# UBC-Thunderbots_PCB_Power__power-v3_1_pc.net
KiCad netlist of a schematic drawn in Altium Designer
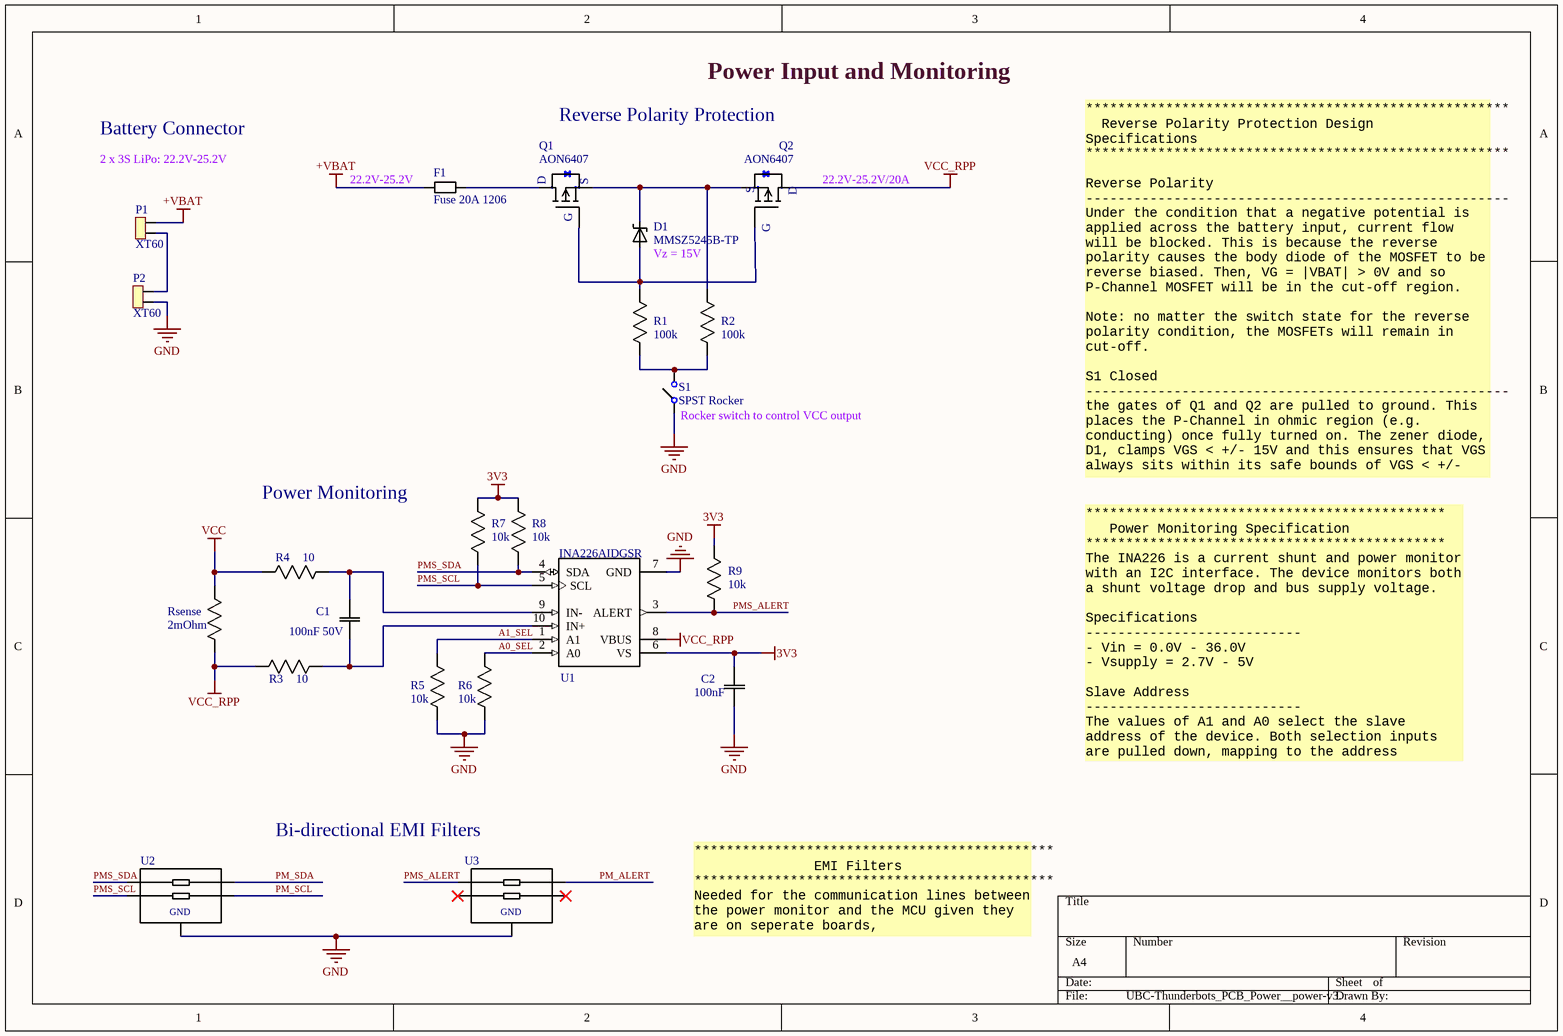
[diagram p0: UBC-Thunderbots_PCB_Power__power-v3.1_pcb__power-io.SchDoc]

(export (version "E")
  (design (tool "Eeschema 10.0.6"))
  (components
    (comp (ref "C1")
      (value "100nF 50V")
      (footprint "0805")
      (description "CAP CER 0.1UF 50V X7R 0805")
      (fields (field (name "MP") "CC0805KRX7R9BB104") (field (name "MF") "Yageo"))
      (libsource (lib "AltiumLibraries") (part "CAP 100nF 0805"))
    )
    (comp (ref "C2")
      (value "100nF")
      (footprint "0805")
      (description "CAP CER 0.1UF 50V X7R 0805")
      (fields (field (name "MP") "CC0805KRX7R9BB104") (field (name "MF") "Yageo"))
      (libsource (lib "AltiumLibraries") (part "CAP 100nF 0805"))
    )
    (comp (ref "D1")
      (value "MMSZ5245B-TP")
      (footprint "SOD-123")
      (description "Zener Diode 15V 500mW ±5% Surface Mount SOD-123")
      (fields (field (name "MP") "MMSZ5224BT1G") (field (name "MF") "ON Semiconductor"))
      (libsource (lib "AltiumLibraries") (part "MMSZ5245B-TP"))
    )
    (comp (ref "F1")
      (value "Fuse 20A 1206")
      (footprint "1206")
      (description "FUSE BOARD MOUNT 20A 32VAC 63VDC")
      (fields (field (name "MF") "Schurter Inc.") (field (name "MP") "3413.0331.22"))
      (libsource (lib "AltiumLibraries") (part "Fuse 20A 1206"))
    )
    (comp (ref "P1")
      (value "XT60")
      (footprint "XT60Connector")
      (description "XT60 CONNECTORS FEMALE PAIR")
      (fields (field (name "MF") "SparkFun Electronics") (field (name "MP") "PRT-10474"))
      (libsource (lib "AltiumLibraries") (part "XT60 Connector"))
    )
    (comp (ref "P2")
      (value "XT60")
      (footprint "XT60Connector")
      (description "XT60 CONNECTORS FEMALE PAIR")
      (fields (field (name "MF") "SparkFun Electronics") (field (name "MP") "PRT-10474"))
      (libsource (lib "AltiumLibraries") (part "XT60 Connector"))
    )
    (comp (ref "Q1")
      (value "AON6407")
      (footprint "8-PowerSMD")
      (description "P-Channel 30V 32A (Ta), 85A (Tc) 7.3W (Ta), 83W (Tc) Surface Mount 8-DFN (5x6)")
      (fields (field (name "MF") "Alpha & Omega Semiconductor Inc."))
      (libsource (lib "AltiumLibraries") (part "AON6407"))
    )
    (comp (ref "Q2")
      (value "AON6407")
      (footprint "8-PowerSMD")
      (description "P-Channel 30V 32A (Ta), 85A (Tc) 7.3W (Ta), 83W (Tc) Surface Mount 8-DFN (5x6)")
      (fields (field (name "MF") "Alpha & Omega Semiconductor Inc."))
      (libsource (lib "AltiumLibraries") (part "AON6407"))
    )
    (comp (ref "R1")
      (value "100k")
      (footprint "0805")
      (description "RES SMD 100K OHM 1% 1/8W 0805")
      (fields (field (name "MP") "RC0805FR-07100KL") (field (name "MF") "Yageo"))
      (libsource (lib "AltiumLibraries") (part "RES 100k 0805"))
    )
    (comp (ref "R2")
      (value "100k")
      (footprint "0805")
      (description "RES SMD 100K OHM 1% 1/8W 0805")
      (fields (field (name "MP") "RC0805FR-07100KL") (field (name "MF") "Yageo"))
      (libsource (lib "AltiumLibraries") (part "RES 100k 0805"))
    )
    (comp (ref "R3")
      (value "10")
      (footprint "0805")
      (description "RES SMD 10 OHM 1% 1/8W 0805")
      (fields (field (name "MP") "RC0805FR-0710RL") (field (name "MF") "Yageo"))
      (libsource (lib "AltiumLibraries") (part "RES 10 0805"))
    )
    (comp (ref "R4")
      (value "10")
      (footprint "0805")
      (description "RES SMD 10 OHM 1% 1/8W 0805")
      (fields (field (name "MP") "RC0805FR-0710RL") (field (name "MF") "Yageo"))
      (libsource (lib "AltiumLibraries") (part "RES 10 0805"))
    )
    (comp (ref "R5")
      (value "10k")
      (footprint "0805")
      (description "RES SMD 10K OHM 1% 1/8W 0805")
      (fields (field (name "TOLERANCE") "1%"))
      (libsource (lib "AltiumLibraries") (part "RES 10k 1/8W"))
    )
    (comp (ref "R6")
      (value "10k")
      (footprint "0805")
      (description "RES SMD 10K OHM 1% 1/8W 0805")
      (fields (field (name "TOLERANCE") "1%"))
      (libsource (lib "AltiumLibraries") (part "RES 10k 1/8W"))
    )
    (comp (ref "R7")
      (value "10k")
      (footprint "0805")
      (description "RES SMD 10K OHM 1% 1/8W 0805")
      (fields (field (name "MP") "RC0805FR-0710KL") (field (name "MF") "Yageo"))
      (libsource (lib "AltiumLibraries") (part "RES 10k 0805"))
    )
    (comp (ref "R8")
      (value "10k")
      (footprint "0805")
      (description "RES SMD 10K OHM 1% 1/8W 0805")
      (fields (field (name "MP") "RC0805FR-0710KL") (field (name "MF") "Yageo"))
      (libsource (lib "AltiumLibraries") (part "RES 10k 0805"))
    )
    (comp (ref "R9")
      (value "10k")
      (footprint "0805")
      (description "RES SMD 10K OHM 1% 1/8W 0805")
      (fields (field (name "MP") "RC0805FR-0710KL") (field (name "MF") "Yageo"))
      (libsource (lib "AltiumLibraries") (part "RES 10k 0805"))
    )
    (comp (ref "Rsense")
      (value "2mOhm")
      (footprint "1206")
      (description "RES 0.002 OHM 1% 1W 1206")
      (fields (field (name "MP") "CSR1206-0R002F1") (field (name "MF") "Riedon"))
      (libsource (lib "AltiumLibraries") (part "RES 2mOhm 1206"))
    )
    (comp (ref "S1")
      (value "SPST Rocker")
      (footprint "SWITCH ROCKER SPST 10A 125V")
      (description "Rocker Switch SPST 10A (AC) 125V Panel Mount, Snap-In")
      (fields (field (name "MP") "SRB22A2FBBNN") (field (name "MF") "ZF Electronics"))
      (libsource (lib "AltiumLibraries") (part "SWITCH ROCKER SPST 10A 125V"))
    )
    (comp (ref "U1")
      (value "INA226AIDGSR")
      (footprint "10-VSSOP")
      (fields (field (name "MF") "Texas Instruments"))
      (libsource (lib "AltiumLibraries") (part "INA226AIDGSR"))
    )
    (comp (ref "U2")
      (value "EMI")
      (footprint "SOT-665")
      (description "RC (Pi) EMI Filter 2nd Order Low Pass 2 Channel R = 100Ohms, C = 19pF (Total)  SOT-665")
      (fields (field (name "MF") "Nexperia USA Inc.") (field (name "MP") "IP4256CZ5-W,115"))
      (libsource (lib "AltiumLibraries") (part "IP4256CZ5-W"))
    )
    (comp (ref "U3")
      (value "EMI")
      (footprint "SOT-665")
      (description "RC (Pi) EMI Filter 2nd Order Low Pass 2 Channel R = 100Ohms, C = 19pF (Total)  SOT-665")
      (fields (field (name "MF") "Nexperia USA Inc.") (field (name "MP") "IP4256CZ5-W,115"))
      (libsource (lib "AltiumLibraries") (part "IP4256CZ5-W"))
    )
  )
  (nets
    (net (code "1") (name "+VBAT") (class "Default")
      (node (ref "F1") (pin "1") (pinfunction "1_1") (pintype "passive"))
      (node (ref "P1") (pin "2") (pinfunction "2_2") (pintype "passive"))
    )
    (net (code "2") (name "/A0_SEL") (class "Default")
      (node (ref "R6") (pin "1") (pinfunction "R1_1") (pintype "passive"))
      (node (ref "U1") (pin "2") (pinfunction "A0_2") (pintype "input"))
    )
    (net (code "3") (name "/A1_SEL") (class "Default")
      (node (ref "R5") (pin "1") (pinfunction "R1_1") (pintype "passive"))
      (node (ref "U1") (pin "1") (pinfunction "A1_1") (pintype "input"))
    )
    (net (code "4") (name "/PMS_ALERT") (class "Default")
      (node (ref "R9") (pin "2") (pinfunction "R2_2") (pintype "passive"))
      (node (ref "U1") (pin "3") (pinfunction "ALERT_3") (pintype "output"))
      (node (ref "U3") (pin "1") (pinfunction "P$1_1") (pintype "passive"))
    )
    (net (code "5") (name "/PMS_SCL") (class "Default")
      (node (ref "R7") (pin "2") (pinfunction "R2_2") (pintype "passive"))
      (node (ref "U1") (pin "5") (pinfunction "SCL_5") (pintype "input"))
      (node (ref "U2") (pin "3") (pinfunction "P$3_3") (pintype "passive"))
    )
    (net (code "6") (name "/PMS_SDA") (class "Default")
      (node (ref "R8") (pin "2") (pinfunction "R2_2") (pintype "passive"))
      (node (ref "U1") (pin "4") (pinfunction "SDA_4") (pintype "bidirectional"))
      (node (ref "U2") (pin "1") (pinfunction "P$1_1") (pintype "passive"))
    )
    (net (code "7") (name "/PM_ALERT") (class "Default")
      (node (ref "U3") (pin "5") (pinfunction "P$5_5") (pintype "passive"))
    )
    (net (code "8") (name "/PM_SCL") (class "Default")
      (node (ref "U2") (pin "4") (pinfunction "P$4_4") (pintype "passive"))
    )
    (net (code "9") (name "/PM_SDA") (class "Default")
      (node (ref "U2") (pin "5") (pinfunction "P$5_5") (pintype "passive"))
    )
    (net (code "10") (name "3V3") (class "Default")
      (node (ref "C2") (pin "2") (pinfunction "C2_2") (pintype "passive"))
      (node (ref "R7") (pin "1") (pinfunction "R1_1") (pintype "passive"))
      (node (ref "R8") (pin "1") (pinfunction "R1_1") (pintype "passive"))
      (node (ref "R9") (pin "1") (pinfunction "R1_1") (pintype "passive"))
      (node (ref "U1") (pin "6") (pinfunction "VS_6") (pintype "power_in"))
    )
    (net (code "11") (name "GND") (class "Default")
      (node (ref "C2") (pin "1") (pinfunction "C1_1") (pintype "passive"))
      (node (ref "P2") (pin "1") (pinfunction "1_1") (pintype "passive"))
      (node (ref "R5") (pin "2") (pinfunction "R2_2") (pintype "passive"))
      (node (ref "R6") (pin "2") (pinfunction "R2_2") (pintype "passive"))
      (node (ref "S1") (pin "0") (pinfunction "0_0") (pintype "passive"))
      (node (ref "U1") (pin "7") (pinfunction "GND_7") (pintype "power_in"))
      (node (ref "U2") (pin "2") (pinfunction "P$2_2") (pintype "passive"))
      (node (ref "U3") (pin "2") (pinfunction "P$2_2") (pintype "passive"))
    )
    (net (code "12") (name "Net-(C1-C1)") (class "Default")
      (node (ref "C1") (pin "1") (pinfunction "C1_1") (pintype "passive"))
      (node (ref "R3") (pin "1") (pinfunction "R1_1") (pintype "passive"))
      (node (ref "U1") (pin "10") (pinfunction "IN+_10") (pintype "input"))
    )
    (net (code "13") (name "Net-(C1-C2)") (class "Default")
      (node (ref "C1") (pin "2") (pinfunction "C2_2") (pintype "passive"))
      (node (ref "R4") (pin "1") (pinfunction "R1_1") (pintype "passive"))
      (node (ref "U1") (pin "9") (pinfunction "IN-_9") (pintype "input"))
    )
    (net (code "14") (name "Net-(F1-Pad2)") (class "Default")
      (node (ref "F1") (pin "2") (pinfunction "2_2") (pintype "passive"))
      (node (ref "Q1") (pin "D") (pinfunction "D_D") (pintype "passive"))
    )
    (net (code "15") (name "Net-(P1-Pad1)") (class "Default")
      (node (ref "P1") (pin "1") (pinfunction "1_1") (pintype "passive"))
      (node (ref "P2") (pin "2") (pinfunction "2_2") (pintype "passive"))
    )
    (net (code "16") (name "Net-(R1-R1)") (class "Default")
      (node (ref "D1") (pin "A") (pinfunction "A_A") (pintype "passive"))
      (node (ref "Q1") (pin "G") (pinfunction "G_G") (pintype "passive"))
      (node (ref "Q2") (pin "G") (pinfunction "G_G") (pintype "passive"))
      (node (ref "R1") (pin "1") (pinfunction "R1_1") (pintype "passive"))
    )
    (net (code "17") (name "Net-(R1-R2)") (class "Default")
      (node (ref "R1") (pin "2") (pinfunction "R2_2") (pintype "passive"))
      (node (ref "R2") (pin "2") (pinfunction "R2_2") (pintype "passive"))
      (node (ref "S1") (pin "1") (pinfunction "1_1") (pintype "passive"))
    )
    (net (code "18") (name "Net-(R2-R1)") (class "Default")
      (node (ref "D1") (pin "C") (pinfunction "C_C") (pintype "passive"))
      (node (ref "Q1") (pin "S") (pinfunction "S_S") (pintype "passive"))
      (node (ref "Q2") (pin "S") (pinfunction "S_S") (pintype "passive"))
      (node (ref "R2") (pin "1") (pinfunction "R1_1") (pintype "passive"))
    )
    (net (code "19") (name "VCC") (class "Default")
      (node (ref "R4") (pin "2") (pinfunction "R2_2") (pintype "passive"))
      (node (ref "Rsense") (pin "1") (pinfunction "R1_1") (pintype "passive"))
    )
    (net (code "20") (name "VCC_RPP") (class "Default")
      (node (ref "Q2") (pin "D") (pinfunction "D_D") (pintype "passive"))
      (node (ref "R3") (pin "2") (pinfunction "R2_2") (pintype "passive"))
      (node (ref "Rsense") (pin "2") (pinfunction "R2_2") (pintype "passive"))
      (node (ref "U1") (pin "8") (pinfunction "VBUS_8") (pintype "power_in"))
    )
    (net (code "21") (name "unconnected-(U3-P$3-Pad3)") (class "Default")
      (node (ref "U3") (pin "3") (pinfunction "P$3_3") (pintype "passive+no_connect"))
    )
    (net (code "22") (name "unconnected-(U3-P$4-Pad4)") (class "Default")
      (node (ref "U3") (pin "4") (pinfunction "P$4_4") (pintype "passive+no_connect"))
    )
  )
)
